# retros.net
KiCad netlist of a schematic drawn in Altium Designer
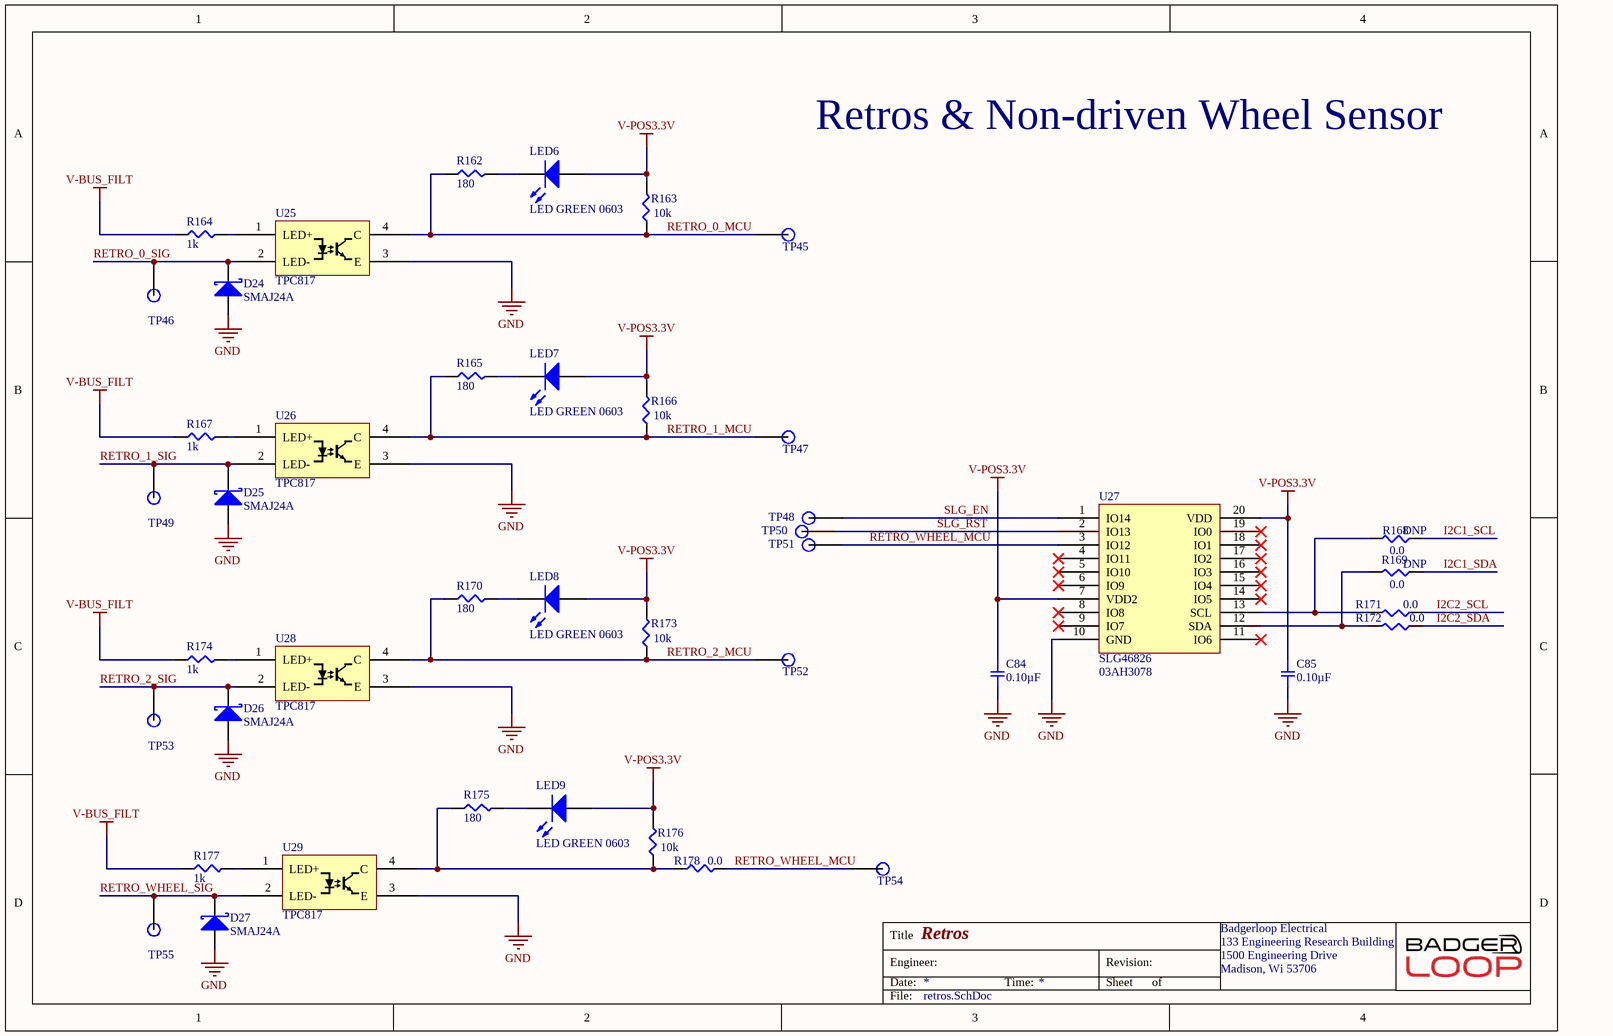
[diagram p0: retros.SchDoc]

(export (version "E")
  (design (tool "Eeschema 10.0.6"))
  (components
    (comp (ref "C84")
      (value "0.10µF")
      (footprint "SMD-0805C")
      (description "CAP CER 0.1UF 25V X7R 0805")
      (fields
        (field (name "DIGI-KEY PART NUMBER") "490-12754-1-ND")
        (field (name "PART NUMBER") "GRM219R71E104KA01D")
      )
      (libsource (lib "capacitors") (part "GRM219R71E104KA01D"))
    )
    (comp (ref "C85")
      (value "0.10µF")
      (footprint "SMD-0805C")
      (description "CAP CER 0.1UF 25V X7R 0805")
      (fields
        (field (name "DIGI-KEY PART NUMBER") "490-12754-1-ND")
        (field (name "PART NUMBER") "GRM219R71E104KA01D")
      )
      (libsource (lib "capacitors") (part "GRM219R71E104KA01D"))
    )
    (comp (ref "D24")
      (value "SMAJ24A")
      (footprint "INDM5026X18N")
      (description "TVS DIODE 24V 38.9V DO214AC")
      (fields (field (name "MANUFACTURER") "LittelFuse Inc"))
      (libsource (lib "misc") (part "SMAJ24A"))
    )
    (comp (ref "D25")
      (value "SMAJ24A")
      (footprint "INDM5026X18N")
      (description "TVS DIODE 24V 38.9V DO214AC")
      (fields (field (name "MANUFACTURER") "LittelFuse Inc"))
      (libsource (lib "misc") (part "SMAJ24A"))
    )
    (comp (ref "D26")
      (value "SMAJ24A")
      (footprint "INDM5026X18N")
      (description "TVS DIODE 24V 38.9V DO214AC")
      (fields (field (name "MANUFACTURER") "LittelFuse Inc"))
      (libsource (lib "misc") (part "SMAJ24A"))
    )
    (comp (ref "D27")
      (value "SMAJ24A")
      (footprint "INDM5026X18N")
      (description "TVS DIODE 24V 38.9V DO214AC")
      (fields (field (name "MANUFACTURER") "LittelFuse Inc"))
      (libsource (lib "misc") (part "SMAJ24A"))
    )
    (comp (ref "LED6")
      (value "LED GREEN 0603")
      (footprint "LED 0603 GREEN")
      (fields (field (name "MANUFACTURER") "Lite-On Inc."))
      (libsource (lib "misc") (part "LED GREEN 0603"))
    )
    (comp (ref "LED7")
      (value "LED GREEN 0603")
      (footprint "LED 0603 GREEN")
      (fields (field (name "MANUFACTURER") "Lite-On Inc."))
      (libsource (lib "misc") (part "LED GREEN 0603"))
    )
    (comp (ref "LED8")
      (value "LED GREEN 0603")
      (footprint "LED 0603 GREEN")
      (fields (field (name "MANUFACTURER") "Lite-On Inc."))
      (libsource (lib "misc") (part "LED GREEN 0603"))
    )
    (comp (ref "LED9")
      (value "LED GREEN 0603")
      (footprint "LED 0603 GREEN")
      (fields (field (name "MANUFACTURER") "Lite-On Inc."))
      (libsource (lib "misc") (part "LED GREEN 0603"))
    )
    (comp (ref "R162")
      (value "180")
      (footprint "SMD-0805-RES")
      (description "RES SMD 180 OHM 1% 1/8W 0805")
      (fields (field (name "PART NUMBER") "ERJ-6ENF1800V") (field (name "DIGI-KEY PART NUMBER") "P180CCT-ND"))
      (libsource (lib "resistors") (part "ERJ-6ENF1800V"))
    )
    (comp (ref "R163")
      (value "10k")
      (footprint "SMD-0805-RES")
      (description "RES SMD 10K OHM 5% 1/8W 0805")
      (fields (field (name "PART NUMBER") "ERJ-6GEYJ103V") (field (name "DIGI-KEY PART NUMBER") "P10KACT-ND"))
      (libsource (lib "resistors") (part "ERJ-6GEYJ103V"))
    )
    (comp (ref "R164")
      (value "1k")
      (footprint "SMD-0805-RES")
      (description "RES SMD 1K OHM 1% 1/8W 0805")
      (fields
        (field (name "PART NUMBER") "ERJ-6ENF1001V")
        (field (name "DIGI-KEY PART NUMBER") "P1.00KCCT-ND")
      )
      (libsource (lib "resistors") (part "ERJ-6ENF1001V"))
    )
    (comp (ref "R165")
      (value "180")
      (footprint "SMD-0805-RES")
      (description "RES SMD 180 OHM 1% 1/8W 0805")
      (fields (field (name "PART NUMBER") "ERJ-6ENF1800V") (field (name "DIGI-KEY PART NUMBER") "P180CCT-ND"))
      (libsource (lib "resistors") (part "ERJ-6ENF1800V"))
    )
    (comp (ref "R166")
      (value "10k")
      (footprint "SMD-0805-RES")
      (description "RES SMD 10K OHM 5% 1/8W 0805")
      (fields (field (name "PART NUMBER") "ERJ-6GEYJ103V") (field (name "DIGI-KEY PART NUMBER") "P10KACT-ND"))
      (libsource (lib "resistors") (part "ERJ-6GEYJ103V"))
    )
    (comp (ref "R167")
      (value "1k")
      (footprint "SMD-0805-RES")
      (description "RES SMD 1K OHM 1% 1/8W 0805")
      (fields
        (field (name "PART NUMBER") "ERJ-6ENF1001V")
        (field (name "DIGI-KEY PART NUMBER") "P1.00KCCT-ND")
      )
      (libsource (lib "resistors") (part "ERJ-6ENF1001V"))
    )
    (comp (ref "R168")
      (value "0.0")
      (footprint "SMD-0805-RES")
      (description "RES SMD 0.0 OHM JUMPER 1/8W 0805")
      (fields
        (field (name "PART NUMBER") "ERJ-6GEY0R00V")
        (field (name "DIGI-KEY PART NUMBER") "P0.0ACT-ND")
        (field (name "DNP") "DNP")
      )
      (libsource (lib "resistors") (part "ERJ-6GEY0R00V"))
    )
    (comp (ref "R169")
      (value "0.0")
      (footprint "SMD-0805-RES")
      (description "RES SMD 0.0 OHM JUMPER 1/8W 0805")
      (fields
        (field (name "PART NUMBER") "ERJ-6GEY0R00V")
        (field (name "DIGI-KEY PART NUMBER") "P0.0ACT-ND")
        (field (name "DNP") "DNP")
      )
      (libsource (lib "resistors") (part "ERJ-6GEY0R00V"))
    )
    (comp (ref "R170")
      (value "180")
      (footprint "SMD-0805-RES")
      (description "RES SMD 180 OHM 1% 1/8W 0805")
      (fields (field (name "PART NUMBER") "ERJ-6ENF1800V") (field (name "DIGI-KEY PART NUMBER") "P180CCT-ND"))
      (libsource (lib "resistors") (part "ERJ-6ENF1800V"))
    )
    (comp (ref "R171")
      (value "0.0")
      (footprint "SMD-0805-RES")
      (description "RES SMD 0.0 OHM JUMPER 1/8W 0805")
      (fields (field (name "PART NUMBER") "ERJ-6GEY0R00V") (field (name "DIGI-KEY PART NUMBER") "P0.0ACT-ND"))
      (libsource (lib "resistors") (part "ERJ-6GEY0R00V"))
    )
    (comp (ref "R172")
      (value "0.0")
      (footprint "SMD-0805-RES")
      (description "RES SMD 0.0 OHM JUMPER 1/8W 0805")
      (fields (field (name "PART NUMBER") "ERJ-6GEY0R00V") (field (name "DIGI-KEY PART NUMBER") "P0.0ACT-ND"))
      (libsource (lib "resistors") (part "ERJ-6GEY0R00V"))
    )
    (comp (ref "R173")
      (value "10k")
      (footprint "SMD-0805-RES")
      (description "RES SMD 10K OHM 5% 1/8W 0805")
      (fields (field (name "PART NUMBER") "ERJ-6GEYJ103V") (field (name "DIGI-KEY PART NUMBER") "P10KACT-ND"))
      (libsource (lib "resistors") (part "ERJ-6GEYJ103V"))
    )
    (comp (ref "R174")
      (value "1k")
      (footprint "SMD-0805-RES")
      (description "RES SMD 1K OHM 1% 1/8W 0805")
      (fields
        (field (name "PART NUMBER") "ERJ-6ENF1001V")
        (field (name "DIGI-KEY PART NUMBER") "P1.00KCCT-ND")
      )
      (libsource (lib "resistors") (part "ERJ-6ENF1001V"))
    )
    (comp (ref "R175")
      (value "180")
      (footprint "SMD-0805-RES")
      (description "RES SMD 180 OHM 1% 1/8W 0805")
      (fields (field (name "PART NUMBER") "ERJ-6ENF1800V") (field (name "DIGI-KEY PART NUMBER") "P180CCT-ND"))
      (libsource (lib "resistors") (part "ERJ-6ENF1800V"))
    )
    (comp (ref "R176")
      (value "10k")
      (footprint "SMD-0805-RES")
      (description "RES SMD 10K OHM 5% 1/8W 0805")
      (fields (field (name "PART NUMBER") "ERJ-6GEYJ103V") (field (name "DIGI-KEY PART NUMBER") "P10KACT-ND"))
      (libsource (lib "resistors") (part "ERJ-6GEYJ103V"))
    )
    (comp (ref "R177")
      (value "1k")
      (footprint "SMD-0805-RES")
      (description "RES SMD 1K OHM 1% 1/8W 0805")
      (fields
        (field (name "PART NUMBER") "ERJ-6ENF1001V")
        (field (name "DIGI-KEY PART NUMBER") "P1.00KCCT-ND")
      )
      (libsource (lib "resistors") (part "ERJ-6ENF1001V"))
    )
    (comp (ref "R178")
      (value "0.0")
      (footprint "SMD-1206-RES")
      (description "RES SMD 0.0 OHM JUMPER 1/4W 1206")
      (fields (field (name "PART NUMBER") "ERJ-8GEY0R00V") (field (name "DIGI-KEY PART NUMBER") "P0.0ECT-ND"))
      (libsource (lib "resistors") (part "ERJ-8GEY0R00V"))
    )
    (comp (ref "TP45")
      (value "TP")
      (footprint "Test Point")
      (description "SMD TEST POINT")
      (libsource (lib "misc") (part "TP"))
    )
    (comp (ref "TP46")
      (value "TP")
      (footprint "Test Point")
      (description "SMD TEST POINT")
      (libsource (lib "misc") (part "TP"))
    )
    (comp (ref "TP47")
      (value "TP")
      (footprint "Test Point")
      (description "SMD TEST POINT")
      (libsource (lib "misc") (part "TP"))
    )
    (comp (ref "TP48")
      (value "TP")
      (footprint "Test Point")
      (description "SMD TEST POINT")
      (libsource (lib "misc") (part "TP"))
    )
    (comp (ref "TP49")
      (value "TP")
      (footprint "Test Point")
      (description "SMD TEST POINT")
      (libsource (lib "misc") (part "TP"))
    )
    (comp (ref "TP50")
      (value "TP")
      (footprint "Test Point")
      (description "SMD TEST POINT")
      (libsource (lib "misc") (part "TP"))
    )
    (comp (ref "TP51")
      (value "TP")
      (footprint "Test Point")
      (description "SMD TEST POINT")
      (libsource (lib "misc") (part "TP"))
    )
    (comp (ref "TP52")
      (value "TP")
      (footprint "Test Point")
      (description "SMD TEST POINT")
      (libsource (lib "misc") (part "TP"))
    )
    (comp (ref "TP53")
      (value "TP")
      (footprint "Test Point")
      (description "SMD TEST POINT")
      (libsource (lib "misc") (part "TP"))
    )
    (comp (ref "TP54")
      (value "TP")
      (footprint "Test Point")
      (description "SMD TEST POINT")
      (libsource (lib "misc") (part "TP"))
    )
    (comp (ref "TP55")
      (value "TP")
      (footprint "Test Point")
      (description "SMD TEST POINT")
      (libsource (lib "misc") (part "TP"))
    )
    (comp (ref "U25")
      (value "TPC817")
      (footprint "SOT200P1005X328-5N")
      (description "OPTOISO 5KV TRANS 4SOP")
      (fields (field (name "MANUFACTURER") "Taiwan Semi"))
      (libsource (lib "ic") (part "TPC817"))
    )
    (comp (ref "U26")
      (value "TPC817")
      (footprint "SOT200P1005X328-5N")
      (description "OPTOISO 5KV TRANS 4SOP")
      (fields (field (name "MANUFACTURER") "Taiwan Semi"))
      (libsource (lib "ic") (part "TPC817"))
    )
    (comp (ref "U27")
      (value "SLG46826")
      (footprint "SOP65P640X175-20N")
      (description "GreenPAK Programmable Mixed Signal Matrix with In-System Programmability")
      (fields
        (field (name "MANUFACTURER") "Dialog Semiconductor")
        (field (name "MANUFACTURER PART NUMBER") "SLG46826V-SKT")
        (field (name "SUPPLIER PART NUMBER 1") "03AH3078")
      )
      (libsource (lib "ic") (part "SLG46826"))
    )
    (comp (ref "U28")
      (value "TPC817")
      (footprint "SOT200P1005X328-5N")
      (description "OPTOISO 5KV TRANS 4SOP")
      (fields (field (name "MANUFACTURER") "Taiwan Semi"))
      (libsource (lib "ic") (part "TPC817"))
    )
    (comp (ref "U29")
      (value "TPC817")
      (footprint "SOT200P1005X328-5N")
      (description "OPTOISO 5KV TRANS 4SOP")
      (fields (field (name "MANUFACTURER") "Taiwan Semi"))
      (libsource (lib "ic") (part "TPC817"))
    )
  )
  (nets
    (net (code "1") (name "/I2C1_SCL") (class "Default")
      (node (ref "R168") (pin "1") (pinfunction "1_1") (pintype "passive"))
    )
    (net (code "2") (name "/I2C1_SDA") (class "Default")
      (node (ref "R169") (pin "1") (pinfunction "1_1") (pintype "passive"))
    )
    (net (code "3") (name "/I2C2_SCL") (class "Default")
      (node (ref "R171") (pin "1") (pinfunction "1_1") (pintype "passive"))
    )
    (net (code "4") (name "/I2C2_SDA") (class "Default")
      (node (ref "R172") (pin "1") (pinfunction "1_1") (pintype "passive"))
    )
    (net (code "5") (name "/RETRO_0_MCU") (class "Default")
      (node (ref "R162") (pin "1") (pinfunction "1_1") (pintype "passive"))
      (node (ref "R163") (pin "1") (pinfunction "1_1") (pintype "passive"))
      (node (ref "TP45") (pin "1") (pinfunction "1_1") (pintype "passive"))
      (node (ref "U25") (pin "4") (pinfunction "C_4") (pintype "passive"))
    )
    (net (code "6") (name "/RETRO_0_SIG") (class "Default")
      (node (ref "D24") (pin "1") (pinfunction "A_1") (pintype "passive"))
      (node (ref "TP46") (pin "1") (pinfunction "1_1") (pintype "passive"))
      (node (ref "U25") (pin "2") (pinfunction "LED-_2") (pintype "passive"))
    )
    (net (code "7") (name "/RETRO_1_MCU") (class "Default")
      (node (ref "R165") (pin "1") (pinfunction "1_1") (pintype "passive"))
      (node (ref "R166") (pin "1") (pinfunction "1_1") (pintype "passive"))
      (node (ref "TP47") (pin "1") (pinfunction "1_1") (pintype "passive"))
      (node (ref "U26") (pin "4") (pinfunction "C_4") (pintype "passive"))
    )
    (net (code "8") (name "/RETRO_1_SIG") (class "Default")
      (node (ref "D25") (pin "1") (pinfunction "A_1") (pintype "passive"))
      (node (ref "TP49") (pin "1") (pinfunction "1_1") (pintype "passive"))
      (node (ref "U26") (pin "2") (pinfunction "LED-_2") (pintype "passive"))
    )
    (net (code "9") (name "/RETRO_2_MCU") (class "Default")
      (node (ref "R170") (pin "1") (pinfunction "1_1") (pintype "passive"))
      (node (ref "R173") (pin "1") (pinfunction "1_1") (pintype "passive"))
      (node (ref "TP52") (pin "1") (pinfunction "1_1") (pintype "passive"))
      (node (ref "U28") (pin "4") (pinfunction "C_4") (pintype "passive"))
    )
    (net (code "10") (name "/RETRO_2_SIG") (class "Default")
      (node (ref "D26") (pin "1") (pinfunction "A_1") (pintype "passive"))
      (node (ref "TP53") (pin "1") (pinfunction "1_1") (pintype "passive"))
      (node (ref "U28") (pin "2") (pinfunction "LED-_2") (pintype "passive"))
    )
    (net (code "11") (name "/RETRO_WHEEL_MCU") (class "Default")
      (node (ref "R178") (pin "2") (pinfunction "2_2") (pintype "passive"))
      (node (ref "TP51") (pin "1") (pinfunction "1_1") (pintype "passive"))
      (node (ref "TP54") (pin "1") (pinfunction "1_1") (pintype "passive"))
      (node (ref "U27") (pin "3") (pinfunction "IO12_3") (pintype "passive"))
    )
    (net (code "12") (name "/RETRO_WHEEL_SIG") (class "Default")
      (node (ref "D27") (pin "1") (pinfunction "A_1") (pintype "passive"))
      (node (ref "TP55") (pin "1") (pinfunction "1_1") (pintype "passive"))
      (node (ref "U29") (pin "2") (pinfunction "LED-_2") (pintype "passive"))
    )
    (net (code "13") (name "/SLG_EN") (class "Default")
      (node (ref "TP48") (pin "1") (pinfunction "1_1") (pintype "passive"))
      (node (ref "U27") (pin "1") (pinfunction "IO14_1") (pintype "passive"))
    )
    (net (code "14") (name "/SLG_RST") (class "Default")
      (node (ref "TP50") (pin "1") (pinfunction "1_1") (pintype "passive"))
      (node (ref "U27") (pin "2") (pinfunction "IO13_2") (pintype "passive"))
    )
    (net (code "15") (name "GND") (class "Default")
      (node (ref "C84") (pin "2") (pinfunction "2_2") (pintype "passive"))
      (node (ref "C85") (pin "2") (pinfunction "2_2") (pintype "passive"))
      (node (ref "D24") (pin "2") (pinfunction "K_2") (pintype "passive"))
      (node (ref "D25") (pin "2") (pinfunction "K_2") (pintype "passive"))
      (node (ref "D26") (pin "2") (pinfunction "K_2") (pintype "passive"))
      (node (ref "D27") (pin "2") (pinfunction "K_2") (pintype "passive"))
      (node (ref "U25") (pin "3") (pinfunction "E_3") (pintype "passive"))
      (node (ref "U26") (pin "3") (pinfunction "E_3") (pintype "passive"))
      (node (ref "U27") (pin "10") (pinfunction "GND_10") (pintype "passive"))
      (node (ref "U28") (pin "3") (pinfunction "E_3") (pintype "passive"))
      (node (ref "U29") (pin "3") (pinfunction "E_3") (pintype "passive"))
    )
    (net (code "16") (name "Net-(LED6-K)") (class "Default")
      (node (ref "LED6") (pin "2") (pinfunction "K_2") (pintype "passive"))
      (node (ref "R162") (pin "2") (pinfunction "2_2") (pintype "passive"))
    )
    (net (code "17") (name "Net-(LED7-K)") (class "Default")
      (node (ref "LED7") (pin "2") (pinfunction "K_2") (pintype "passive"))
      (node (ref "R165") (pin "2") (pinfunction "2_2") (pintype "passive"))
    )
    (net (code "18") (name "Net-(LED8-K)") (class "Default")
      (node (ref "LED8") (pin "2") (pinfunction "K_2") (pintype "passive"))
      (node (ref "R170") (pin "2") (pinfunction "2_2") (pintype "passive"))
    )
    (net (code "19") (name "Net-(LED9-K)") (class "Default")
      (node (ref "LED9") (pin "2") (pinfunction "K_2") (pintype "passive"))
      (node (ref "R175") (pin "2") (pinfunction "2_2") (pintype "passive"))
    )
    (net (code "20") (name "Net-(U25-LED+)") (class "Default")
      (node (ref "R164") (pin "2") (pinfunction "2_2") (pintype "passive"))
      (node (ref "U25") (pin "1") (pinfunction "LED+_1") (pintype "passive"))
    )
    (net (code "21") (name "Net-(U26-LED+)") (class "Default")
      (node (ref "R167") (pin "2") (pinfunction "2_2") (pintype "passive"))
      (node (ref "U26") (pin "1") (pinfunction "LED+_1") (pintype "passive"))
    )
    (net (code "22") (name "Net-(U27-SCL)") (class "Default")
      (node (ref "R168") (pin "2") (pinfunction "2_2") (pintype "passive"))
      (node (ref "R171") (pin "2") (pinfunction "2_2") (pintype "passive"))
      (node (ref "U27") (pin "13") (pinfunction "SCL_13") (pintype "passive"))
    )
    (net (code "23") (name "Net-(U27-SDA)") (class "Default")
      (node (ref "R169") (pin "2") (pinfunction "2_2") (pintype "passive"))
      (node (ref "R172") (pin "2") (pinfunction "2_2") (pintype "passive"))
      (node (ref "U27") (pin "12") (pinfunction "SDA_12") (pintype "passive"))
    )
    (net (code "24") (name "Net-(U28-LED+)") (class "Default")
      (node (ref "R174") (pin "2") (pinfunction "2_2") (pintype "passive"))
      (node (ref "U28") (pin "1") (pinfunction "LED+_1") (pintype "passive"))
    )
    (net (code "25") (name "Net-(U29-C)") (class "Default")
      (node (ref "R175") (pin "1") (pinfunction "1_1") (pintype "passive"))
      (node (ref "R176") (pin "1") (pinfunction "1_1") (pintype "passive"))
      (node (ref "R178") (pin "1") (pinfunction "1_1") (pintype "passive"))
      (node (ref "U29") (pin "4") (pinfunction "C_4") (pintype "passive"))
    )
    (net (code "26") (name "Net-(U29-LED+)") (class "Default")
      (node (ref "R177") (pin "2") (pinfunction "2_2") (pintype "passive"))
      (node (ref "U29") (pin "1") (pinfunction "LED+_1") (pintype "passive"))
    )
    (net (code "27") (name "V-BUS_FILT") (class "Default")
      (node (ref "R164") (pin "1") (pinfunction "1_1") (pintype "passive"))
      (node (ref "R167") (pin "1") (pinfunction "1_1") (pintype "passive"))
      (node (ref "R174") (pin "1") (pinfunction "1_1") (pintype "passive"))
      (node (ref "R177") (pin "1") (pinfunction "1_1") (pintype "passive"))
    )
    (net (code "28") (name "V-POS3.3V") (class "Default")
      (node (ref "C84") (pin "1") (pinfunction "1_1") (pintype "passive"))
      (node (ref "C85") (pin "1") (pinfunction "1_1") (pintype "passive"))
      (node (ref "LED6") (pin "1") (pinfunction "A_1") (pintype "passive"))
      (node (ref "LED7") (pin "1") (pinfunction "A_1") (pintype "passive"))
      (node (ref "LED8") (pin "1") (pinfunction "A_1") (pintype "passive"))
      (node (ref "LED9") (pin "1") (pinfunction "A_1") (pintype "passive"))
      (node (ref "R163") (pin "2") (pinfunction "2_2") (pintype "passive"))
      (node (ref "R166") (pin "2") (pinfunction "2_2") (pintype "passive"))
      (node (ref "R173") (pin "2") (pinfunction "2_2") (pintype "passive"))
      (node (ref "R176") (pin "2") (pinfunction "2_2") (pintype "passive"))
      (node (ref "U27") (pin "20") (pinfunction "VDD_20") (pintype "passive"))
      (node (ref "U27") (pin "7") (pinfunction "VDD2_7") (pintype "passive"))
    )
    (net (code "29") (name "unconnected-(U27-IO0-Pad19)") (class "Default")
      (node (ref "U27") (pin "19") (pinfunction "IO0_19") (pintype "passive+no_connect"))
    )
    (net (code "30") (name "unconnected-(U27-IO1-Pad18)") (class "Default")
      (node (ref "U27") (pin "18") (pinfunction "IO1_18") (pintype "passive+no_connect"))
    )
    (net (code "31") (name "unconnected-(U27-IO2-Pad17)") (class "Default")
      (node (ref "U27") (pin "17") (pinfunction "IO2_17") (pintype "passive+no_connect"))
    )
    (net (code "32") (name "unconnected-(U27-IO3-Pad16)") (class "Default")
      (node (ref "U27") (pin "16") (pinfunction "IO3_16") (pintype "passive+no_connect"))
    )
    (net (code "33") (name "unconnected-(U27-IO4-Pad15)") (class "Default")
      (node (ref "U27") (pin "15") (pinfunction "IO4_15") (pintype "passive+no_connect"))
    )
    (net (code "34") (name "unconnected-(U27-IO5-Pad14)") (class "Default")
      (node (ref "U27") (pin "14") (pinfunction "IO5_14") (pintype "passive+no_connect"))
    )
    (net (code "35") (name "unconnected-(U27-IO6-Pad11)") (class "Default")
      (node (ref "U27") (pin "11") (pinfunction "IO6_11") (pintype "passive+no_connect"))
    )
    (net (code "36") (name "unconnected-(U27-IO7-Pad9)") (class "Default")
      (node (ref "U27") (pin "9") (pinfunction "IO7_9") (pintype "passive+no_connect"))
    )
    (net (code "37") (name "unconnected-(U27-IO8-Pad8)") (class "Default")
      (node (ref "U27") (pin "8") (pinfunction "IO8_8") (pintype "passive+no_connect"))
    )
    (net (code "38") (name "unconnected-(U27-IO9-Pad6)") (class "Default")
      (node (ref "U27") (pin "6") (pinfunction "IO9_6") (pintype "passive+no_connect"))
    )
    (net (code "39") (name "unconnected-(U27-IO10-Pad5)") (class "Default")
      (node (ref "U27") (pin "5") (pinfunction "IO10_5") (pintype "passive+no_connect"))
    )
    (net (code "40") (name "unconnected-(U27-IO11-Pad4)") (class "Default")
      (node (ref "U27") (pin "4") (pinfunction "IO11_4") (pintype "passive+no_connect"))
    )
  )
)
